# IDC_MCX_Adapter.net
KiCad netlist of a schematic drawn in Altium Designer
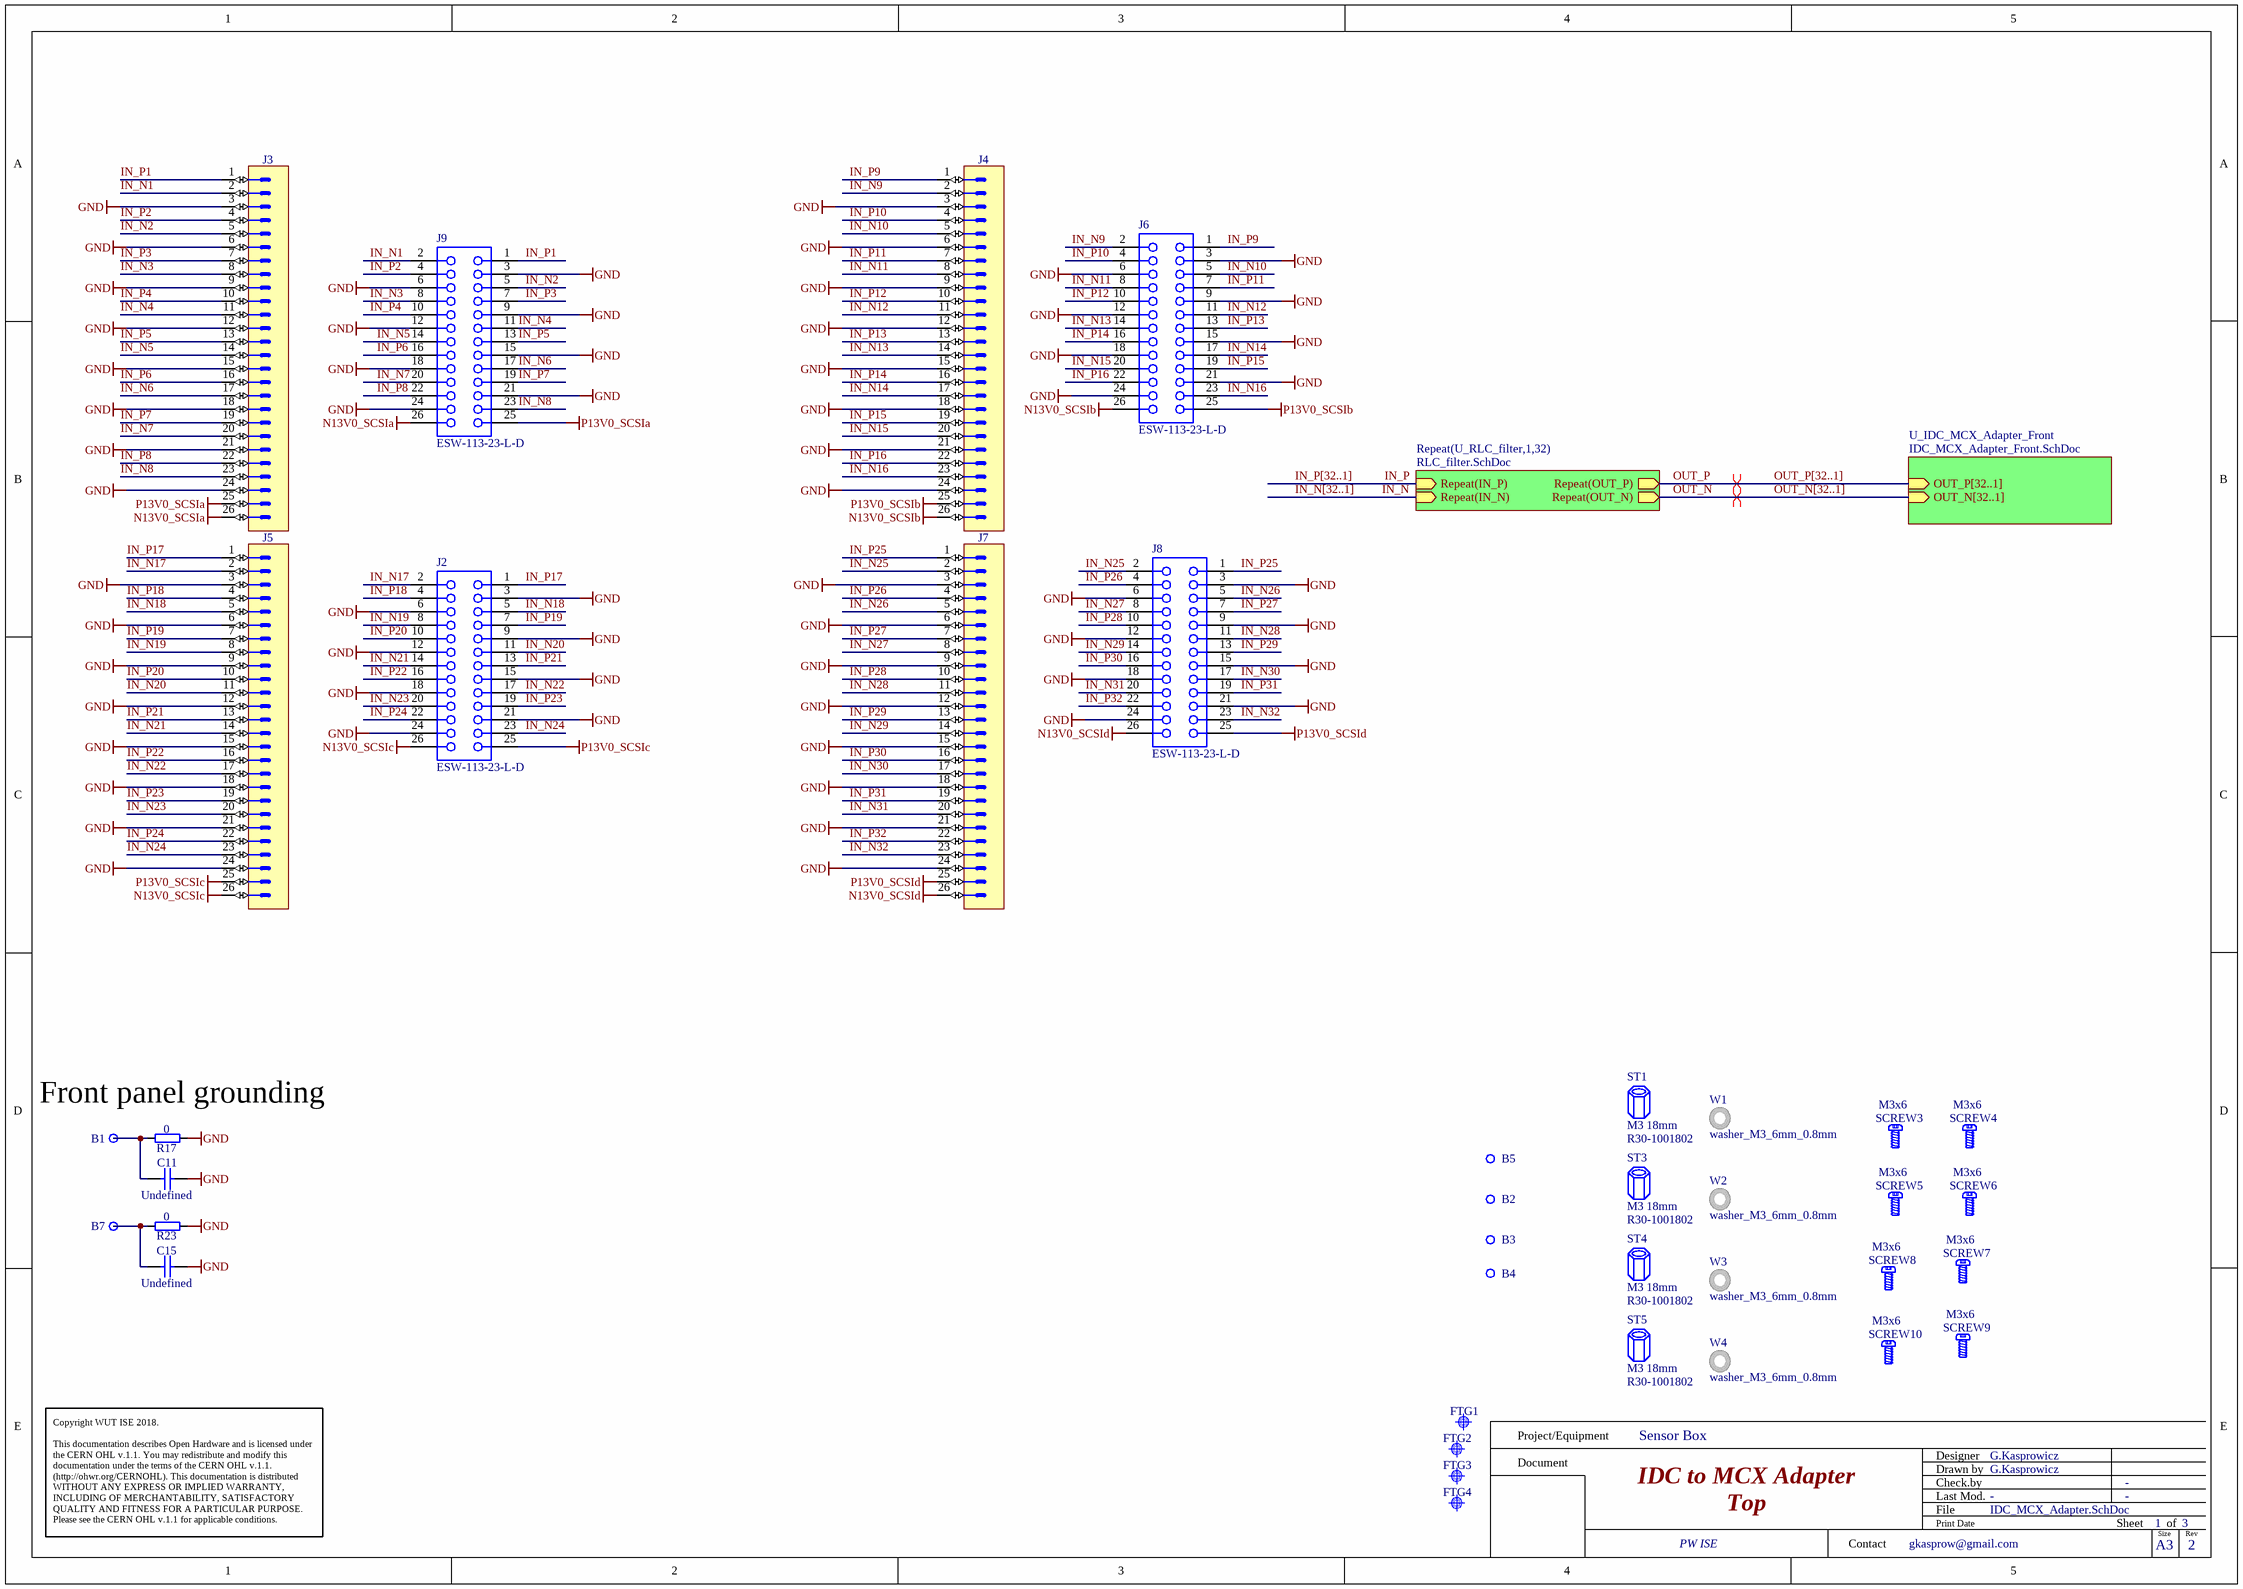
[diagram p0: IDC_MCX_Adapter.SchDoc]

(export (version "E")
  (design (tool "Eeschema 10.0.6"))
  (components
    (comp (ref "B1")
      (value "Plated Hole")
      (footprint "MTG270_500")
      (description "Single Terminal Socket")
      (fields (field (name "PART NUMBER") "PLATED_HOLE2.7_PAD5.0") (field (name "AUTHOR") "CERN DEM JMW"))
      (libsource (lib "Eletro-mechanical") (part "Single Terminal Socket"))
    )
    (comp (ref "B2")
      (value "Plated Hole")
      (footprint "MTG320_700")
      (description "Single Terminal Socket")
      (fields (field (name "PART NUMBER") "PLATED_HOLE3.2_PAD7.0") (field (name "AUTHOR") "CERN DEM JMW"))
      (libsource (lib "Eletro-mechanical") (part "Single Terminal Socket"))
    )
    (comp (ref "B3")
      (value "Plated Hole")
      (footprint "MTG320_700")
      (description "Single Terminal Socket")
      (fields (field (name "PART NUMBER") "PLATED_HOLE3.2_PAD7.0") (field (name "AUTHOR") "CERN DEM JMW"))
      (libsource (lib "Eletro-mechanical") (part "Single Terminal Socket"))
    )
    (comp (ref "B4")
      (value "Plated Hole")
      (footprint "MTG320_700")
      (description "Single Terminal Socket")
      (fields (field (name "PART NUMBER") "PLATED_HOLE3.2_PAD7.0") (field (name "AUTHOR") "CERN DEM JMW"))
      (libsource (lib "Eletro-mechanical") (part "Single Terminal Socket"))
    )
    (comp (ref "B5")
      (value "Plated Hole")
      (footprint "MTG320_700")
      (description "Single Terminal Socket")
      (fields (field (name "PART NUMBER") "PLATED_HOLE3.2_PAD7.0") (field (name "AUTHOR") "CERN DEM JMW"))
      (libsource (lib "Eletro-mechanical") (part "Single Terminal Socket"))
    )
    (comp (ref "B7")
      (value "Plated Hole")
      (footprint "MTG270_500")
      (description "Single Terminal Socket")
      (fields (field (name "PART NUMBER") "PLATED_HOLE2.7_PAD5.0") (field (name "AUTHOR") "CERN DEM JMW"))
      (libsource (lib "Eletro-mechanical") (part "Single Terminal Socket"))
    )
    (comp (ref "C11")
      (value "Undefined")
      (footprint "CAPC2012X135N")
      (description "Non-polarised capacitor")
      (fields (field (name "PART NUMBER") "CC0805_NO-VALUE") (field (name "AUTHOR") "CERN DEM JLC"))
      (libsource (lib "Capacitors") (part "Capacitor - non polarized"))
    )
    (comp (ref "C15")
      (value "Undefined")
      (footprint "CAPC2012X135N")
      (description "Non-polarised capacitor")
      (fields (field (name "PART NUMBER") "CC0805_NO-VALUE") (field (name "AUTHOR") "CERN DEM JLC"))
      (libsource (lib "Capacitors") (part "Capacitor - non polarized"))
    )
    (comp (ref "FTG1")
      (value "Use only in PCB")
      (footprint "FIDUCIAL_TOP_C100-200")
      (description "Fiducial Target")
      (fields (field (name "PART NUMBER") "FIDUCIAL_TARGET_C100-200") (field (name "AUTHOR") "CERN DEM JLC"))
      (libsource (lib "Eletro-mechanical") (part "Fiducial Target"))
    )
    (comp (ref "FTG2")
      (value "Use only in PCB")
      (footprint "FIDUCIAL_TOP_S100-200")
      (description "Fiducial Target")
      (fields (field (name "PART NUMBER") "FIDUCIAL_TARGET_S100-200") (field (name "AUTHOR") "CERN DEM JLC"))
      (libsource (lib "Eletro-mechanical") (part "Fiducial Target"))
    )
    (comp (ref "FTG3")
      (value "Use only in PCB")
      (footprint "FIDUCIAL_TOP_S100-200")
      (description "Fiducial Target")
      (fields (field (name "PART NUMBER") "FIDUCIAL_TARGET_S100-200") (field (name "AUTHOR") "CERN DEM JLC"))
      (libsource (lib "Eletro-mechanical") (part "Fiducial Target"))
    )
    (comp (ref "FTG4")
      (value "Use only in PCB")
      (footprint "FIDUCIAL_TOP_S100-200")
      (description "Fiducial Target")
      (fields (field (name "PART NUMBER") "FIDUCIAL_TARGET_S100-200") (field (name "AUTHOR") "CERN DEM JLC"))
      (libsource (lib "Eletro-mechanical") (part "Fiducial Target"))
    )
    (comp (ref "J2")
      (value "ESW-113-23-L-D")
      (footprint "SMTC-ESW-113-23-X-D")
      (description "Elevated Socket, Through-hole, Vertical, -55 to 125 degC, 2.54 mm Pitch, 26-Pin, Female, RoHS")
      (fields (field (name "MANUFACTURER") "Samtec"))
      (libsource (lib "Altium Content Vault") (part "SMTC-ESW-113-X-X-D"))
    )
    (comp (ref "J3")
      (value "Header 26")
      (footprint "3M_N2526-6002RB")
      (description "Connector 26 Male")
      (fields
        (field (name "PART NUMBER") "3M_N2526-6002RB")
        (field (name "MANUFACTURER") "3M")
        (field (name "AUTHOR") "CERN DEM JLC")
      )
      (libsource (lib "Connectors") (part "Connector 26 Male"))
    )
    (comp (ref "J4")
      (value "Header 26")
      (footprint "3M_N2526-6002RB")
      (description "Connector 26 Male")
      (fields
        (field (name "PART NUMBER") "3M_N2526-6002RB")
        (field (name "MANUFACTURER") "3M")
        (field (name "AUTHOR") "CERN DEM JLC")
      )
      (libsource (lib "Connectors") (part "Connector 26 Male"))
    )
    (comp (ref "J5")
      (value "Header 26")
      (footprint "3M_N2526-6002RB")
      (description "Connector 26 Male")
      (fields
        (field (name "PART NUMBER") "3M_N2526-6002RB")
        (field (name "MANUFACTURER") "3M")
        (field (name "AUTHOR") "CERN DEM JLC")
      )
      (libsource (lib "Connectors") (part "Connector 26 Male"))
    )
    (comp (ref "J6")
      (value "ESW-113-23-L-D")
      (footprint "SMTC-ESW-113-23-X-D")
      (description "Elevated Socket, Through-hole, Vertical, -55 to 125 degC, 2.54 mm Pitch, 26-Pin, Female, RoHS")
      (fields (field (name "MANUFACTURER") "Samtec"))
      (libsource (lib "Altium Content Vault") (part "SMTC-ESW-113-X-X-D"))
    )
    (comp (ref "J7")
      (value "Header 26")
      (footprint "3M_N2526-6002RB")
      (description "Connector 26 Male")
      (fields
        (field (name "PART NUMBER") "3M_N2526-6002RB")
        (field (name "MANUFACTURER") "3M")
        (field (name "AUTHOR") "CERN DEM JLC")
      )
      (libsource (lib "Connectors") (part "Connector 26 Male"))
    )
    (comp (ref "J8")
      (value "ESW-113-23-L-D")
      (footprint "SMTC-ESW-113-23-X-D")
      (description "Elevated Socket, Through-hole, Vertical, -55 to 125 degC, 2.54 mm Pitch, 26-Pin, Female, RoHS")
      (fields (field (name "MANUFACTURER") "Samtec"))
      (libsource (lib "Altium Content Vault") (part "SMTC-ESW-113-X-X-D"))
    )
    (comp (ref "J9")
      (value "ESW-113-23-L-D")
      (footprint "SMTC-ESW-113-23-X-D")
      (description "Elevated Socket, Through-hole, Vertical, -55 to 125 degC, 2.54 mm Pitch, 26-Pin, Female, RoHS")
      (fields (field (name "MANUFACTURER") "Samtec"))
      (libsource (lib "Altium Content Vault") (part "SMTC-ESW-113-X-X-D"))
    )
    (comp (ref "R17")
      (value "0")
      (footprint "RESC1608X55N")
      (description "Resistor")
      (fields
        (field (name "PART NUMBER") "R0603_0R_JUMPER")
        (field (name "MANUFACTURER") "GENERIC")
        (field (name "AUTHOR") "CERN DEM JLC")
      )
      (libsource (lib "Resistors") (part "Resistor"))
    )
    (comp (ref "R23")
      (value "0")
      (footprint "RESC1608X55N")
      (description "Resistor")
      (fields
        (field (name "PART NUMBER") "R0603_0R_JUMPER")
        (field (name "MANUFACTURER") "GENERIC")
        (field (name "AUTHOR") "CERN DEM JLC")
      )
      (libsource (lib "Resistors") (part "Resistor"))
    )
    (comp (ref "SCREW3")
      (value "M3x6")
      (footprint "BOSSARD_BN5687-3061605_v")
      (description "Screw")
      (fields
        (field (name "PART NUMBER") "BOSSARD_BN5687-3061605_v")
        (field (name "MANUFACTURER") "BOSSARD")
        (field (name "AUTHOR") "CERN DEM JLC")
      )
      (libsource (lib "Eletro-mechanical") (part "Screw"))
    )
    (comp (ref "SCREW4")
      (value "M3x6")
      (footprint "BOSSARD_BN5687-3061605_v")
      (description "Screw")
      (fields
        (field (name "PART NUMBER") "BOSSARD_BN5687-3061605_v")
        (field (name "MANUFACTURER") "BOSSARD")
        (field (name "AUTHOR") "CERN DEM JLC")
      )
      (libsource (lib "Eletro-mechanical") (part "Screw"))
    )
    (comp (ref "SCREW5")
      (value "M3x6")
      (footprint "BOSSARD_BN5687-3061605_v")
      (description "Screw")
      (fields
        (field (name "PART NUMBER") "BOSSARD_BN5687-3061605_v")
        (field (name "MANUFACTURER") "BOSSARD")
        (field (name "AUTHOR") "CERN DEM JLC")
      )
      (libsource (lib "Eletro-mechanical") (part "Screw"))
    )
    (comp (ref "SCREW6")
      (value "M3x6")
      (footprint "BOSSARD_BN5687-3061605_v")
      (description "Screw")
      (fields
        (field (name "PART NUMBER") "BOSSARD_BN5687-3061605_v")
        (field (name "MANUFACTURER") "BOSSARD")
        (field (name "AUTHOR") "CERN DEM JLC")
      )
      (libsource (lib "Eletro-mechanical") (part "Screw"))
    )
    (comp (ref "SCREW7")
      (value "M3x6")
      (footprint "BOSSARD_BN5687-3061605_v")
      (description "Screw")
      (fields
        (field (name "PART NUMBER") "BOSSARD_BN5687-3061605_v")
        (field (name "MANUFACTURER") "BOSSARD")
        (field (name "AUTHOR") "CERN DEM JLC")
      )
      (libsource (lib "Eletro-mechanical") (part "Screw"))
    )
    (comp (ref "SCREW8")
      (value "M3x6")
      (footprint "BOSSARD_BN5687-3061605_v")
      (description "Screw")
      (fields
        (field (name "PART NUMBER") "BOSSARD_BN5687-3061605_v")
        (field (name "MANUFACTURER") "BOSSARD")
        (field (name "AUTHOR") "CERN DEM JLC")
      )
      (libsource (lib "Eletro-mechanical") (part "Screw"))
    )
    (comp (ref "SCREW9")
      (value "M3x6")
      (footprint "BOSSARD_BN5687-3061605_v")
      (description "Screw")
      (fields
        (field (name "PART NUMBER") "BOSSARD_BN5687-3061605_v")
        (field (name "MANUFACTURER") "BOSSARD")
        (field (name "AUTHOR") "CERN DEM JLC")
      )
      (libsource (lib "Eletro-mechanical") (part "Screw"))
    )
    (comp (ref "SCREW10")
      (value "M3x6")
      (footprint "BOSSARD_BN5687-3061605_v")
      (description "Screw")
      (fields
        (field (name "PART NUMBER") "BOSSARD_BN5687-3061605_v")
        (field (name "MANUFACTURER") "BOSSARD")
        (field (name "AUTHOR") "CERN DEM JLC")
      )
      (libsource (lib "Eletro-mechanical") (part "Screw"))
    )
    (comp (ref "ST1")
      (value "M3 18mm")
      (footprint "R30-1001802")
      (description "M3.0x18 standoff")
      (fields (field (name "MANUFACTURER") "Harwin") (field (name "MANUFACTURER PART NUMBER") "R30-1001802"))
      (libsource (lib "mechanical") (part "STANDOFF_HARWIN_R30_1001802"))
    )
    (comp (ref "ST3")
      (value "M3 18mm")
      (footprint "R30-1001802")
      (description "M3.0x18 standoff")
      (fields (field (name "MANUFACTURER") "Harwin") (field (name "MANUFACTURER PART NUMBER") "R30-1001802"))
      (libsource (lib "mechanical") (part "STANDOFF_HARWIN_R30_1001802"))
    )
    (comp (ref "ST4")
      (value "M3 18mm")
      (footprint "R30-1001802")
      (description "M3.0x18 standoff")
      (fields (field (name "MANUFACTURER") "Harwin") (field (name "MANUFACTURER PART NUMBER") "R30-1001802"))
      (libsource (lib "mechanical") (part "STANDOFF_HARWIN_R30_1001802"))
    )
    (comp (ref "ST5")
      (value "M3 18mm")
      (footprint "R30-1001802")
      (description "M3.0x18 standoff")
      (fields (field (name "MANUFACTURER") "Harwin") (field (name "MANUFACTURER PART NUMBER") "R30-1001802"))
      (libsource (lib "mechanical") (part "STANDOFF_HARWIN_R30_1001802"))
    )
    (comp (ref "W1")
      (value "washer_M3_6mm_0.8mm")
      (footprint "washer_M3_6mm_0.8mm")
      (description "M3 Washer:\r\nID: 3.2mm\r\nOD: 6mm\r\nThickness 0.8mm")
      (fields
        (field (name "MANUFACTURER") "Accu Limited")
        (field (name "MANUFACTURER PART NUMBER") "HAFZ-M3-A4")
      )
      (libsource (lib "mechanical") (part "washer_M3_6mm_0.8mm"))
    )
    (comp (ref "W2")
      (value "washer_M3_6mm_0.8mm")
      (footprint "washer_M3_6mm_0.8mm")
      (description "M3 Washer:\r\nID: 3.2mm\r\nOD: 6mm\r\nThickness 0.8mm")
      (fields
        (field (name "MANUFACTURER") "Accu Limited")
        (field (name "MANUFACTURER PART NUMBER") "HAFZ-M3-A4")
      )
      (libsource (lib "mechanical") (part "washer_M3_6mm_0.8mm"))
    )
    (comp (ref "W3")
      (value "washer_M3_6mm_0.8mm")
      (footprint "washer_M3_6mm_0.8mm")
      (description "M3 Washer:\r\nID: 3.2mm\r\nOD: 6mm\r\nThickness 0.8mm")
      (fields
        (field (name "MANUFACTURER") "Accu Limited")
        (field (name "MANUFACTURER PART NUMBER") "HAFZ-M3-A4")
      )
      (libsource (lib "mechanical") (part "washer_M3_6mm_0.8mm"))
    )
    (comp (ref "W4")
      (value "washer_M3_6mm_0.8mm")
      (footprint "washer_M3_6mm_0.8mm")
      (description "M3 Washer:\r\nID: 3.2mm\r\nOD: 6mm\r\nThickness 0.8mm")
      (fields
        (field (name "MANUFACTURER") "Accu Limited")
        (field (name "MANUFACTURER PART NUMBER") "HAFZ-M3-A4")
      )
      (libsource (lib "mechanical") (part "washer_M3_6mm_0.8mm"))
    )
  )
  (nets
    (net (code "66") (name "/IN_N1") (class "Default")
      (node (ref "J3") (pin "2") (pinfunction "2_2") (pintype "bidirectional"))
      (node (ref "J9") (pin "2") (pinfunction "2_2") (pintype "passive"))
    )
    (net (code "67") (name "/IN_N2") (class "Default")
      (node (ref "J3") (pin "5") (pinfunction "5_5") (pintype "bidirectional"))
      (node (ref "J9") (pin "5") (pinfunction "5_5") (pintype "passive"))
    )
    (net (code "68") (name "/IN_N3") (class "Default")
      (node (ref "J3") (pin "8") (pinfunction "8_8") (pintype "bidirectional"))
      (node (ref "J9") (pin "8") (pinfunction "8_8") (pintype "passive"))
    )
    (net (code "69") (name "/IN_N4") (class "Default")
      (node (ref "J3") (pin "11") (pinfunction "11_11") (pintype "bidirectional"))
      (node (ref "J9") (pin "11") (pinfunction "11_11") (pintype "passive"))
    )
    (net (code "70") (name "/IN_N5") (class "Default")
      (node (ref "J3") (pin "14") (pinfunction "14_14") (pintype "bidirectional"))
      (node (ref "J9") (pin "14") (pinfunction "14_14") (pintype "passive"))
    )
    (net (code "71") (name "/IN_N6") (class "Default")
      (node (ref "J3") (pin "17") (pinfunction "17_17") (pintype "bidirectional"))
      (node (ref "J9") (pin "17") (pinfunction "17_17") (pintype "passive"))
    )
    (net (code "72") (name "/IN_N7") (class "Default")
      (node (ref "J3") (pin "20") (pinfunction "20_20") (pintype "bidirectional"))
      (node (ref "J9") (pin "20") (pinfunction "20_20") (pintype "passive"))
    )
    (net (code "73") (name "/IN_N8") (class "Default")
      (node (ref "J3") (pin "23") (pinfunction "23_23") (pintype "bidirectional"))
      (node (ref "J9") (pin "23") (pinfunction "23_23") (pintype "passive"))
    )
    (net (code "74") (name "/IN_N9") (class "Default")
      (node (ref "J4") (pin "2") (pinfunction "2_2") (pintype "bidirectional"))
      (node (ref "J6") (pin "2") (pinfunction "2_2") (pintype "passive"))
    )
    (net (code "75") (name "/IN_N10") (class "Default")
      (node (ref "J4") (pin "5") (pinfunction "5_5") (pintype "bidirectional"))
      (node (ref "J6") (pin "5") (pinfunction "5_5") (pintype "passive"))
    )
    (net (code "76") (name "/IN_N11") (class "Default")
      (node (ref "J4") (pin "8") (pinfunction "8_8") (pintype "bidirectional"))
      (node (ref "J6") (pin "8") (pinfunction "8_8") (pintype "passive"))
    )
    (net (code "77") (name "/IN_N12") (class "Default")
      (node (ref "J4") (pin "11") (pinfunction "11_11") (pintype "bidirectional"))
      (node (ref "J6") (pin "11") (pinfunction "11_11") (pintype "passive"))
    )
    (net (code "78") (name "/IN_N13") (class "Default")
      (node (ref "J4") (pin "14") (pinfunction "14_14") (pintype "bidirectional"))
      (node (ref "J6") (pin "14") (pinfunction "14_14") (pintype "passive"))
    )
    (net (code "79") (name "/IN_N14") (class "Default")
      (node (ref "J4") (pin "17") (pinfunction "17_17") (pintype "bidirectional"))
      (node (ref "J6") (pin "17") (pinfunction "17_17") (pintype "passive"))
    )
    (net (code "80") (name "/IN_N15") (class "Default")
      (node (ref "J4") (pin "20") (pinfunction "20_20") (pintype "bidirectional"))
      (node (ref "J6") (pin "20") (pinfunction "20_20") (pintype "passive"))
    )
    (net (code "81") (name "/IN_N16") (class "Default")
      (node (ref "J4") (pin "23") (pinfunction "23_23") (pintype "bidirectional"))
      (node (ref "J6") (pin "23") (pinfunction "23_23") (pintype "passive"))
    )
    (net (code "82") (name "/IN_N17") (class "Default")
      (node (ref "J2") (pin "2") (pinfunction "2_2") (pintype "passive"))
      (node (ref "J5") (pin "2") (pinfunction "2_2") (pintype "bidirectional"))
    )
    (net (code "83") (name "/IN_N18") (class "Default")
      (node (ref "J2") (pin "5") (pinfunction "5_5") (pintype "passive"))
      (node (ref "J5") (pin "5") (pinfunction "5_5") (pintype "bidirectional"))
    )
    (net (code "84") (name "/IN_N19") (class "Default")
      (node (ref "J2") (pin "8") (pinfunction "8_8") (pintype "passive"))
      (node (ref "J5") (pin "8") (pinfunction "8_8") (pintype "bidirectional"))
    )
    (net (code "85") (name "/IN_N20") (class "Default")
      (node (ref "J2") (pin "11") (pinfunction "11_11") (pintype "passive"))
      (node (ref "J5") (pin "11") (pinfunction "11_11") (pintype "bidirectional"))
    )
    (net (code "86") (name "/IN_N21") (class "Default")
      (node (ref "J2") (pin "14") (pinfunction "14_14") (pintype "passive"))
      (node (ref "J5") (pin "14") (pinfunction "14_14") (pintype "bidirectional"))
    )
    (net (code "87") (name "/IN_N22") (class "Default")
      (node (ref "J2") (pin "17") (pinfunction "17_17") (pintype "passive"))
      (node (ref "J5") (pin "17") (pinfunction "17_17") (pintype "bidirectional"))
    )
    (net (code "88") (name "/IN_N23") (class "Default")
      (node (ref "J2") (pin "20") (pinfunction "20_20") (pintype "passive"))
      (node (ref "J5") (pin "20") (pinfunction "20_20") (pintype "bidirectional"))
    )
    (net (code "89") (name "/IN_N24") (class "Default")
      (node (ref "J2") (pin "23") (pinfunction "23_23") (pintype "passive"))
      (node (ref "J5") (pin "23") (pinfunction "23_23") (pintype "bidirectional"))
    )
    (net (code "90") (name "/IN_N25") (class "Default")
      (node (ref "J7") (pin "2") (pinfunction "2_2") (pintype "bidirectional"))
      (node (ref "J8") (pin "2") (pinfunction "2_2") (pintype "passive"))
    )
    (net (code "91") (name "/IN_N26") (class "Default")
      (node (ref "J7") (pin "5") (pinfunction "5_5") (pintype "bidirectional"))
      (node (ref "J8") (pin "5") (pinfunction "5_5") (pintype "passive"))
    )
    (net (code "92") (name "/IN_N27") (class "Default")
      (node (ref "J7") (pin "8") (pinfunction "8_8") (pintype "bidirectional"))
      (node (ref "J8") (pin "8") (pinfunction "8_8") (pintype "passive"))
    )
    (net (code "93") (name "/IN_N28") (class "Default")
      (node (ref "J7") (pin "11") (pinfunction "11_11") (pintype "bidirectional"))
      (node (ref "J8") (pin "11") (pinfunction "11_11") (pintype "passive"))
    )
    (net (code "94") (name "/IN_N29") (class "Default")
      (node (ref "J7") (pin "14") (pinfunction "14_14") (pintype "bidirectional"))
      (node (ref "J8") (pin "14") (pinfunction "14_14") (pintype "passive"))
    )
    (net (code "95") (name "/IN_N30") (class "Default")
      (node (ref "J7") (pin "17") (pinfunction "17_17") (pintype "bidirectional"))
      (node (ref "J8") (pin "17") (pinfunction "17_17") (pintype "passive"))
    )
    (net (code "96") (name "/IN_N31") (class "Default")
      (node (ref "J7") (pin "20") (pinfunction "20_20") (pintype "bidirectional"))
      (node (ref "J8") (pin "20") (pinfunction "20_20") (pintype "passive"))
    )
    (net (code "97") (name "/IN_N32") (class "Default")
      (node (ref "J7") (pin "23") (pinfunction "23_23") (pintype "bidirectional"))
      (node (ref "J8") (pin "23") (pinfunction "23_23") (pintype "passive"))
    )
    (net (code "100") (name "/IN_P1") (class "Default")
      (node (ref "J3") (pin "1") (pinfunction "1_1") (pintype "bidirectional"))
      (node (ref "J9") (pin "1") (pinfunction "1_1") (pintype "passive"))
    )
    (net (code "101") (name "/IN_P2") (class "Default")
      (node (ref "J3") (pin "4") (pinfunction "4_4") (pintype "bidirectional"))
      (node (ref "J9") (pin "4") (pinfunction "4_4") (pintype "passive"))
    )
    (net (code "102") (name "/IN_P3") (class "Default")
      (node (ref "J3") (pin "7") (pinfunction "7_7") (pintype "bidirectional"))
      (node (ref "J9") (pin "7") (pinfunction "7_7") (pintype "passive"))
    )
    (net (code "103") (name "/IN_P4") (class "Default")
      (node (ref "J3") (pin "10") (pinfunction "10_10") (pintype "bidirectional"))
      (node (ref "J9") (pin "10") (pinfunction "10_10") (pintype "passive"))
    )
    (net (code "104") (name "/IN_P5") (class "Default")
      (node (ref "J3") (pin "13") (pinfunction "13_13") (pintype "bidirectional"))
      (node (ref "J9") (pin "13") (pinfunction "13_13") (pintype "passive"))
    )
    (net (code "105") (name "/IN_P6") (class "Default")
      (node (ref "J3") (pin "16") (pinfunction "16_16") (pintype "bidirectional"))
      (node (ref "J9") (pin "16") (pinfunction "16_16") (pintype "passive"))
    )
    (net (code "106") (name "/IN_P7") (class "Default")
      (node (ref "J3") (pin "19") (pinfunction "19_19") (pintype "bidirectional"))
      (node (ref "J9") (pin "19") (pinfunction "19_19") (pintype "passive"))
    )
    (net (code "107") (name "/IN_P8") (class "Default")
      (node (ref "J3") (pin "22") (pinfunction "22_22") (pintype "bidirectional"))
      (node (ref "J9") (pin "22") (pinfunction "22_22") (pintype "passive"))
    )
    (net (code "108") (name "/IN_P9") (class "Default")
      (node (ref "J4") (pin "1") (pinfunction "1_1") (pintype "bidirectional"))
      (node (ref "J6") (pin "1") (pinfunction "1_1") (pintype "passive"))
    )
    (net (code "109") (name "/IN_P10") (class "Default")
      (node (ref "J4") (pin "4") (pinfunction "4_4") (pintype "bidirectional"))
      (node (ref "J6") (pin "4") (pinfunction "4_4") (pintype "passive"))
    )
    (net (code "110") (name "/IN_P11") (class "Default")
      (node (ref "J4") (pin "7") (pinfunction "7_7") (pintype "bidirectional"))
      (node (ref "J6") (pin "7") (pinfunction "7_7") (pintype "passive"))
    )
    (net (code "111") (name "/IN_P12") (class "Default")
      (node (ref "J4") (pin "10") (pinfunction "10_10") (pintype "bidirectional"))
      (node (ref "J6") (pin "10") (pinfunction "10_10") (pintype "passive"))
    )
    (net (code "112") (name "/IN_P13") (class "Default")
      (node (ref "J4") (pin "13") (pinfunction "13_13") (pintype "bidirectional"))
      (node (ref "J6") (pin "13") (pinfunction "13_13") (pintype "passive"))
    )
    (net (code "113") (name "/IN_P14") (class "Default")
      (node (ref "J4") (pin "16") (pinfunction "16_16") (pintype "bidirectional"))
      (node (ref "J6") (pin "16") (pinfunction "16_16") (pintype "passive"))
    )
    (net (code "114") (name "/IN_P15") (class "Default")
      (node (ref "J4") (pin "19") (pinfunction "19_19") (pintype "bidirectional"))
      (node (ref "J6") (pin "19") (pinfunction "19_19") (pintype "passive"))
    )
    (net (code "115") (name "/IN_P16") (class "Default")
      (node (ref "J4") (pin "22") (pinfunction "22_22") (pintype "bidirectional"))
      (node (ref "J6") (pin "22") (pinfunction "22_22") (pintype "passive"))
    )
    (net (code "116") (name "/IN_P17") (class "Default")
      (node (ref "J2") (pin "1") (pinfunction "1_1") (pintype "passive"))
      (node (ref "J5") (pin "1") (pinfunction "1_1") (pintype "bidirectional"))
    )
    (net (code "117") (name "/IN_P18") (class "Default")
      (node (ref "J2") (pin "4") (pinfunction "4_4") (pintype "passive"))
      (node (ref "J5") (pin "4") (pinfunction "4_4") (pintype "bidirectional"))
    )
    (net (code "118") (name "/IN_P19") (class "Default")
      (node (ref "J2") (pin "7") (pinfunction "7_7") (pintype "passive"))
      (node (ref "J5") (pin "7") (pinfunction "7_7") (pintype "bidirectional"))
    )
    (net (code "119") (name "/IN_P20") (class "Default")
      (node (ref "J2") (pin "10") (pinfunction "10_10") (pintype "passive"))
      (node (ref "J5") (pin "10") (pinfunction "10_10") (pintype "bidirectional"))
    )
    (net (code "120") (name "/IN_P21") (class "Default")
      (node (ref "J2") (pin "13") (pinfunction "13_13") (pintype "passive"))
      (node (ref "J5") (pin "13") (pinfunction "13_13") (pintype "bidirectional"))
    )
    (net (code "121") (name "/IN_P22") (class "Default")
      (node (ref "J2") (pin "16") (pinfunction "16_16") (pintype "passive"))
      (node (ref "J5") (pin "16") (pinfunction "16_16") (pintype "bidirectional"))
    )
    (net (code "122") (name "/IN_P23") (class "Default")
      (node (ref "J2") (pin "19") (pinfunction "19_19") (pintype "passive"))
      (node (ref "J5") (pin "19") (pinfunction "19_19") (pintype "bidirectional"))
    )
    (net (code "123") (name "/IN_P24") (class "Default")
      (node (ref "J2") (pin "22") (pinfunction "22_22") (pintype "passive"))
      (node (ref "J5") (pin "22") (pinfunction "22_22") (pintype "bidirectional"))
    )
    (net (code "124") (name "/IN_P25") (class "Default")
      (node (ref "J7") (pin "1") (pinfunction "1_1") (pintype "bidirectional"))
      (node (ref "J8") (pin "1") (pinfunction "1_1") (pintype "passive"))
    )
    (net (code "125") (name "/IN_P26") (class "Default")
      (node (ref "J7") (pin "4") (pinfunction "4_4") (pintype "bidirectional"))
      (node (ref "J8") (pin "4") (pinfunction "4_4") (pintype "passive"))
    )
    (net (code "126") (name "/IN_P27") (class "Default")
      (node (ref "J7") (pin "7") (pinfunction "7_7") (pintype "bidirectional"))
      (node (ref "J8") (pin "7") (pinfunction "7_7") (pintype "passive"))
    )
    (net (code "127") (name "/IN_P28") (class "Default")
      (node (ref "J7") (pin "10") (pinfunction "10_10") (pintype "bidirectional"))
      (node (ref "J8") (pin "10") (pinfunction "10_10") (pintype "passive"))
    )
    (net (code "128") (name "/IN_P29") (class "Default")
      (node (ref "J7") (pin "13") (pinfunction "13_13") (pintype "bidirectional"))
      (node (ref "J8") (pin "13") (pinfunction "13_13") (pintype "passive"))
    )
    (net (code "129") (name "/IN_P30") (class "Default")
      (node (ref "J7") (pin "16") (pinfunction "16_16") (pintype "bidirectional"))
      (node (ref "J8") (pin "16") (pinfunction "16_16") (pintype "passive"))
    )
    (net (code "130") (name "/IN_P31") (class "Default")
      (node (ref "J7") (pin "19") (pinfunction "19_19") (pintype "bidirectional"))
      (node (ref "J8") (pin "19") (pinfunction "19_19") (pintype "passive"))
    )
    (net (code "131") (name "/IN_P32") (class "Default")
      (node (ref "J7") (pin "22") (pinfunction "22_22") (pintype "bidirectional"))
      (node (ref "J8") (pin "22") (pinfunction "22_22") (pintype "passive"))
    )
    (net (code "137") (name "GND") (class "Default")
      (node (ref "C11") (pin "2") (pinfunction "2_2") (pintype "passive"))
      (node (ref "C15") (pin "2") (pinfunction "2_2") (pintype "passive"))
      (node (ref "J2") (pin "12") (pinfunction "12_12") (pintype "passive"))
      (node (ref "J2") (pin "15") (pinfunction "15_15") (pintype "passive"))
      (node (ref "J2") (pin "18") (pinfunction "18_18") (pintype "passive"))
      (node (ref "J2") (pin "21") (pinfunction "21_21") (pintype "passive"))
      (node (ref "J2") (pin "24") (pinfunction "24_24") (pintype "passive"))
      (node (ref "J2") (pin "3") (pinfunction "3_3") (pintype "passive"))
      (node (ref "J2") (pin "6") (pinfunction "6_6") (pintype "passive"))
      (node (ref "J2") (pin "9") (pinfunction "9_9") (pintype "passive"))
      (node (ref "J3") (pin "12") (pinfunction "12_12") (pintype "bidirectional"))
      (node (ref "J3") (pin "15") (pinfunction "15_15") (pintype "bidirectional"))
      (node (ref "J3") (pin "18") (pinfunction "18_18") (pintype "bidirectional"))
      (node (ref "J3") (pin "21") (pinfunction "21_21") (pintype "bidirectional"))
      (node (ref "J3") (pin "24") (pinfunction "24_24") (pintype "bidirectional"))
      (node (ref "J3") (pin "3") (pinfunction "3_3") (pintype "bidirectional"))
      (node (ref "J3") (pin "6") (pinfunction "6_6") (pintype "bidirectional"))
      (node (ref "J3") (pin "9") (pinfunction "9_9") (pintype "bidirectional"))
      (node (ref "J4") (pin "12") (pinfunction "12_12") (pintype "bidirectional"))
      (node (ref "J4") (pin "15") (pinfunction "15_15") (pintype "bidirectional"))
      (node (ref "J4") (pin "18") (pinfunction "18_18") (pintype "bidirectional"))
      (node (ref "J4") (pin "21") (pinfunction "21_21") (pintype "bidirectional"))
      (node (ref "J4") (pin "24") (pinfunction "24_24") (pintype "bidirectional"))
      (node (ref "J4") (pin "3") (pinfunction "3_3") (pintype "bidirectional"))
      (node (ref "J4") (pin "6") (pinfunction "6_6") (pintype "bidirectional"))
      (node (ref "J4") (pin "9") (pinfunction "9_9") (pintype "bidirectional"))
      (node (ref "J5") (pin "12") (pinfunction "12_12") (pintype "bidirectional"))
      (node (ref "J5") (pin "15") (pinfunction "15_15") (pintype "bidirectional"))
      (node (ref "J5") (pin "18") (pinfunction "18_18") (pintype "bidirectional"))
      (node (ref "J5") (pin "21") (pinfunction "21_21") (pintype "bidirectional"))
      (node (ref "J5") (pin "24") (pinfunction "24_24") (pintype "bidirectional"))
      (node (ref "J5") (pin "3") (pinfunction "3_3") (pintype "bidirectional"))
      (node (ref "J5") (pin "6") (pinfunction "6_6") (pintype "bidirectional"))
      (node (ref "J5") (pin "9") (pinfunction "9_9") (pintype "bidirectional"))
      (node (ref "J6") (pin "12") (pinfunction "12_12") (pintype "passive"))
      (node (ref "J6") (pin "15") (pinfunction "15_15") (pintype "passive"))
      (node (ref "J6") (pin "18") (pinfunction "18_18") (pintype "passive"))
      (node (ref "J6") (pin "21") (pinfunction "21_21") (pintype "passive"))
      (node (ref "J6") (pin "24") (pinfunction "24_24") (pintype "passive"))
      (node (ref "J6") (pin "3") (pinfunction "3_3") (pintype "passive"))
      (node (ref "J6") (pin "6") (pinfunction "6_6") (pintype "passive"))
      (node (ref "J6") (pin "9") (pinfunction "9_9") (pintype "passive"))
      (node (ref "J7") (pin "12") (pinfunction "12_12") (pintype "bidirectional"))
      (node (ref "J7") (pin "15") (pinfunction "15_15") (pintype "bidirectional"))
      (node (ref "J7") (pin "18") (pinfunction "18_18") (pintype "bidirectional"))
      (node (ref "J7") (pin "21") (pinfunction "21_21") (pintype "bidirectional"))
      (node (ref "J7") (pin "24") (pinfunction "24_24") (pintype "bidirectional"))
      (node (ref "J7") (pin "3") (pinfunction "3_3") (pintype "bidirectional"))
      (node (ref "J7") (pin "6") (pinfunction "6_6") (pintype "bidirectional"))
      (node (ref "J7") (pin "9") (pinfunction "9_9") (pintype "bidirectional"))
      (node (ref "J8") (pin "12") (pinfunction "12_12") (pintype "passive"))
      (node (ref "J8") (pin "15") (pinfunction "15_15") (pintype "passive"))
      (node (ref "J8") (pin "18") (pinfunction "18_18") (pintype "passive"))
      (node (ref "J8") (pin "21") (pinfunction "21_21") (pintype "passive"))
      (node (ref "J8") (pin "24") (pinfunction "24_24") (pintype "passive"))
      (node (ref "J8") (pin "3") (pinfunction "3_3") (pintype "passive"))
      (node (ref "J8") (pin "6") (pinfunction "6_6") (pintype "passive"))
      (node (ref "J8") (pin "9") (pinfunction "9_9") (pintype "passive"))
      (node (ref "J9") (pin "12") (pinfunction "12_12") (pintype "passive"))
      (node (ref "J9") (pin "15") (pinfunction "15_15") (pintype "passive"))
      (node (ref "J9") (pin "18") (pinfunction "18_18") (pintype "passive"))
      (node (ref "J9") (pin "21") (pinfunction "21_21") (pintype "passive"))
      (node (ref "J9") (pin "24") (pinfunction "24_24") (pintype "passive"))
      (node (ref "J9") (pin "3") (pinfunction "3_3") (pintype "passive"))
      (node (ref "J9") (pin "6") (pinfunction "6_6") (pintype "passive"))
      (node (ref "J9") (pin "9") (pinfunction "9_9") (pintype "passive"))
      (node (ref "R17") (pin "1") (pinfunction "1_1") (pintype "passive"))
      (node (ref "R23") (pin "1") (pinfunction "1_1") (pintype "passive"))
    )
    (net (code "138") (name "N13V0_SCSIa") (class "Default")
      (node (ref "J3") (pin "26") (pinfunction "26_26") (pintype "bidirectional"))
      (node (ref "J9") (pin "26") (pinfunction "26_26") (pintype "passive"))
    )
    (net (code "139") (name "N13V0_SCSIb") (class "Default")
      (node (ref "J4") (pin "26") (pinfunction "26_26") (pintype "bidirectional"))
      (node (ref "J6") (pin "26") (pinfunction "26_26") (pintype "passive"))
    )
    (net (code "140") (name "N13V0_SCSIc") (class "Default")
      (node (ref "J2") (pin "26") (pinfunction "26_26") (pintype "passive"))
      (node (ref "J5") (pin "26") (pinfunction "26_26") (pintype "bidirectional"))
    )
    (net (code "141") (name "N13V0_SCSId") (class "Default")
      (node (ref "J7") (pin "26") (pinfunction "26_26") (pintype "bidirectional"))
      (node (ref "J8") (pin "26") (pinfunction "26_26") (pintype "passive"))
    )
    (net (code "142") (name "Net-(B1-Pad1)") (class "Default")
      (node (ref "B1") (pin "1") (pinfunction "1_1") (pintype "bidirectional"))
      (node (ref "C11") (pin "1") (pinfunction "1_1") (pintype "passive"))
      (node (ref "R17") (pin "2") (pinfunction "2_2") (pintype "passive"))
    )
    (net (code "143") (name "Net-(B7-Pad1)") (class "Default")
      (node (ref "B7") (pin "1") (pinfunction "1_1") (pintype "bidirectional"))
      (node (ref "C15") (pin "1") (pinfunction "1_1") (pintype "passive"))
      (node (ref "R23") (pin "2") (pinfunction "2_2") (pintype "passive"))
    )
    (net (code "144") (name "P13V0_SCSIa") (class "Default")
      (node (ref "J3") (pin "25") (pinfunction "25_25") (pintype "bidirectional"))
      (node (ref "J9") (pin "25") (pinfunction "25_25") (pintype "passive"))
    )
    (net (code "145") (name "P13V0_SCSIb") (class "Default")
      (node (ref "J4") (pin "25") (pinfunction "25_25") (pintype "bidirectional"))
      (node (ref "J6") (pin "25") (pinfunction "25_25") (pintype "passive"))
    )
    (net (code "146") (name "P13V0_SCSIc") (class "Default")
      (node (ref "J2") (pin "25") (pinfunction "25_25") (pintype "passive"))
      (node (ref "J5") (pin "25") (pinfunction "25_25") (pintype "bidirectional"))
    )
    (net (code "147") (name "P13V0_SCSId") (class "Default")
      (node (ref "J7") (pin "25") (pinfunction "25_25") (pintype "bidirectional"))
      (node (ref "J8") (pin "25") (pinfunction "25_25") (pintype "passive"))
    )
    (net (code "148") (name "unconnected-(B2-Pad1)") (class "Default")
      (node (ref "B2") (pin "1") (pinfunction "1_1") (pintype "bidirectional"))
    )
    (net (code "149") (name "unconnected-(B3-Pad1)") (class "Default")
      (node (ref "B3") (pin "1") (pinfunction "1_1") (pintype "bidirectional"))
    )
    (net (code "150") (name "unconnected-(B4-Pad1)") (class "Default")
      (node (ref "B4") (pin "1") (pinfunction "1_1") (pintype "bidirectional"))
    )
    (net (code "151") (name "unconnected-(B5-Pad1)") (class "Default")
      (node (ref "B5") (pin "1") (pinfunction "1_1") (pintype "bidirectional"))
    )
  )
)
